# Sheet1.net
KiCad netlist of a schematic drawn in Altium Designer
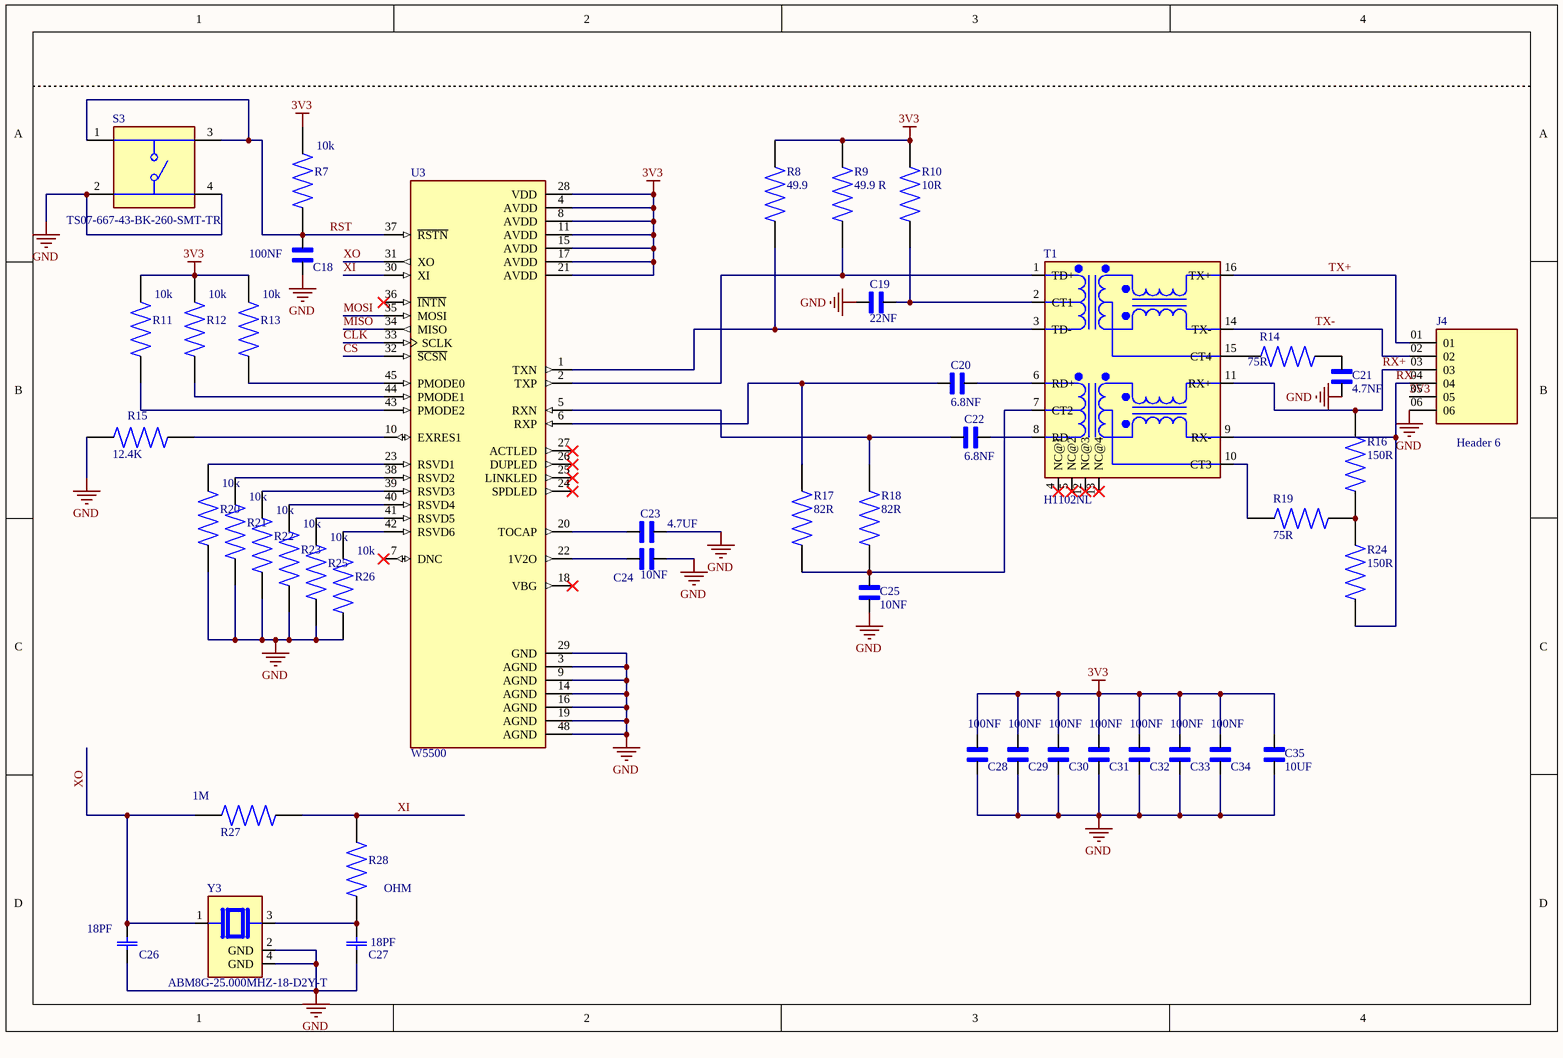
[diagram p0: Sheet1.SchDoc]

(export (version "E")
  (design (tool "Eeschema 10.0.6"))
  (components
    (comp (ref "C18")
      (value "100NF")
      (footprint "CAPC1608X90")
      (fields (field (name "MF") "KEMET") (field (name "MP") "C0603C104J3RACTU"))
      (libsource (lib "Accelo Integrated_Library") (part "C0603C104J3RACTU"))
    )
    (comp (ref "C19")
      (value "22NF")
      (footprint "CAPC1608X90")
      (fields (field (name "MF") "KEMET") (field (name "MP") "C0603C104J3RACTU"))
      (libsource (lib "") (part "C0603C104J3RACTU_1"))
    )
    (comp (ref "C20")
      (value "6.8NF")
      (footprint "CAPC1608X90")
      (fields (field (name "MF") "KEMET") (field (name "MP") "C0603C104J3RACTU"))
      (libsource (lib "") (part "C0603C104J3RACTU_1"))
    )
    (comp (ref "C21")
      (value "4.7NF")
      (footprint "CAPC1608X90")
      (fields (field (name "MF") "KEMET") (field (name "MP") "C0603C104J3RACTU"))
      (libsource (lib "") (part "C0603C104J3RACTU_2"))
    )
    (comp (ref "C22")
      (value "6.8NF")
      (footprint "CAPC1608X90")
      (fields (field (name "MF") "KEMET") (field (name "MP") "C0603C104J3RACTU"))
      (libsource (lib "") (part "C0603C104J3RACTU_1"))
    )
    (comp (ref "C23")
      (value "4.7UF")
      (footprint "CAPC2012X135N")
      (description "4.7礔 卤10% 10V Ceramic Capacitor X7R 0805 (2012 Metric)")
      (fields (field (name "MF") "Samsung") (field (name "MP") "CL21B225KPFNNNG"))
      (libsource (lib "") (part "CL21B225KPFNNNG_1"))
    )
    (comp (ref "C24")
      (value "10NF")
      (footprint "CAPC1608X90")
      (fields (field (name "MF") "KEMET") (field (name "MP") "C0603C104J3RACTU"))
      (libsource (lib "") (part "C0603C104J3RACTU_1"))
    )
    (comp (ref "C25")
      (value "10NF")
      (footprint "CAPC1608X90")
      (fields (field (name "MF") "KEMET") (field (name "MP") "C0603C104J3RACTU"))
      (libsource (lib "") (part "C0603C104J3RACTU_2"))
    )
    (comp (ref "C26")
      (value "18PF")
      (footprint "CAPC1608X85N")
      (description "18 pF ±5% 50V Ceramic Capacitor C0G, NP0 0603 (1608 Metric)")
      (fields (field (name "MF") "KEMET") (field (name "MP") "C0603C200J5GACTU"))
      (libsource (lib "Accelo Integrated_Library") (part "C0603C200J5GACTU"))
    )
    (comp (ref "C27")
      (value "18PF")
      (footprint "CAPC1608X85N")
      (description "18 pF ±5% 50V Ceramic Capacitor C0G, NP0 0603 (1608 Metric)")
      (fields (field (name "MF") "KEMET") (field (name "MP") "C0603C200J5GACTU"))
      (libsource (lib "Accelo Integrated_Library") (part "C0603C200J5GACTU"))
    )
    (comp (ref "C28")
      (value "100NF")
      (footprint "CAPC1608X90")
      (fields (field (name "MF") "KEMET") (field (name "MP") "C0603C104J3RACTU"))
      (libsource (lib "Accelo Integrated_Library") (part "C0603C104J3RACTU"))
    )
    (comp (ref "C29")
      (value "100NF")
      (footprint "CAPC1608X90")
      (fields (field (name "MF") "KEMET") (field (name "MP") "C0603C104J3RACTU"))
      (libsource (lib "Accelo Integrated_Library") (part "C0603C104J3RACTU"))
    )
    (comp (ref "C30")
      (value "100NF")
      (footprint "CAPC1608X90")
      (fields (field (name "MF") "KEMET") (field (name "MP") "C0603C104J3RACTU"))
      (libsource (lib "Accelo Integrated_Library") (part "C0603C104J3RACTU"))
    )
    (comp (ref "C31")
      (value "100NF")
      (footprint "CAPC1608X90")
      (fields (field (name "MF") "KEMET") (field (name "MP") "C0603C104J3RACTU"))
      (libsource (lib "Accelo Integrated_Library") (part "C0603C104J3RACTU"))
    )
    (comp (ref "C32")
      (value "100NF")
      (footprint "CAPC1608X90")
      (fields (field (name "MF") "KEMET") (field (name "MP") "C0603C104J3RACTU"))
      (libsource (lib "Accelo Integrated_Library") (part "C0603C104J3RACTU"))
    )
    (comp (ref "C33")
      (value "100NF")
      (footprint "CAPC1608X90")
      (fields (field (name "MF") "KEMET") (field (name "MP") "C0603C104J3RACTU"))
      (libsource (lib "Accelo Integrated_Library") (part "C0603C104J3RACTU"))
    )
    (comp (ref "C34")
      (value "100NF")
      (footprint "CAPC1608X90")
      (fields (field (name "MF") "KEMET") (field (name "MP") "C0603C104J3RACTU"))
      (libsource (lib "Accelo Integrated_Library") (part "C0603C104J3RACTU"))
    )
    (comp (ref "C35")
      (value "10UF")
      (footprint "CAPC2012X135N")
      (description "10 礔 卤10% 10V Ceramic Capacitor X7R 0805 (2012 Metric)")
      (fields (field (name "MF") "Samsung") (field (name "MP") "CL21B225KPFNNNG"))
      (libsource (lib "Accelo Integrated_Library") (part "CL21B225KPFNNNG"))
    )
    (comp (ref "J4")
      (value "Header 6")
      (footprint "SAMTEC_MTLW-106-06-G-S-180")
      (fields (field (name "MP") "MTLW-106-06-G-S-180"))
      (libsource (lib "MTLW-106-06-G-S-180") (part "MTLW-106-06-G-S-180"))
    )
    (comp (ref "R7")
      (value "10k")
      (footprint "RESC3116X65N")
      (description "10 kOhms ±1% 0.25W, 1/4W Chip Resistor 1206 (3216 Metric) Moisture Resistant Thick Film")
      (fields (field (name "MF") "Yageo") (field (name "MP") "AC1206FR-070RL"))
      (libsource (lib "Accelo Integrated_Library") (part "AC1206FR-070RL"))
    )
    (comp (ref "R8")
      (value "49.9")
      (footprint "RESC3116X65N")
      (description "49.9 Ohms ±1% 0.25W, 1/4W Chip Resistor 1206 (3216 Metric) Moisture Resistant Thick Film")
      (fields (field (name "MF") "Yageo") (field (name "MP") "AC1206FR-070RL"))
      (libsource (lib "Accelo Integrated_Library") (part "AC1206FR-070RL"))
    )
    (comp (ref "R9")
      (value "49.9 R")
      (footprint "RESC3116X65N")
      (description "49.9 Ohms ±1% 0.25W, 1/4W Chip Resistor 1206 (3216 Metric) Moisture Resistant Thick Film")
      (fields (field (name "MF") "Yageo") (field (name "MP") "AC1206FR-070RL"))
      (libsource (lib "Accelo Integrated_Library") (part "AC1206FR-070RL"))
    )
    (comp (ref "R10")
      (value "10R")
      (footprint "RESC3116X65N")
      (description "10 Ohms ±1% 0.25W, 1/4W Chip Resistor 1206 (3216 Metric) Moisture Resistant Thick Film")
      (fields (field (name "MF") "Yageo") (field (name "MP") "AC1206FR-070RL"))
      (libsource (lib "Accelo Integrated_Library") (part "AC1206FR-070RL"))
    )
    (comp (ref "R11")
      (value "10k")
      (footprint "RESC3116X65N")
      (description "10 kOhms ±1% 0.25W, 1/4W Chip Resistor 1206 (3216 Metric) Moisture Resistant Thick Film")
      (fields (field (name "MF") "Yageo") (field (name "MP") "AC1206FR-070RL"))
      (libsource (lib "Accelo Integrated_Library") (part "AC1206FR-070RL"))
    )
    (comp (ref "R12")
      (value "10k")
      (footprint "RESC3116X65N")
      (description "10 kOhms ±1% 0.25W, 1/4W Chip Resistor 1206 (3216 Metric) Moisture Resistant Thick Film")
      (fields (field (name "MF") "Yageo") (field (name "MP") "AC1206FR-070RL"))
      (libsource (lib "Accelo Integrated_Library") (part "AC1206FR-070RL"))
    )
    (comp (ref "R13")
      (value "10k")
      (footprint "RESC3116X65N")
      (description "10 kOhms ±1% 0.25W, 1/4W Chip Resistor 1206 (3216 Metric) Moisture Resistant Thick Film")
      (fields (field (name "MF") "Yageo") (field (name "MP") "AC1206FR-070RL"))
      (libsource (lib "Accelo Integrated_Library") (part "AC1206FR-070RL"))
    )
    (comp (ref "R14")
      (value "75R")
      (footprint "RESC3116X65N")
      (description "75 Ohms Jumper Chip Resistor 1206 (3216 Metric) Automotive AEC-Q200 Thick Film")
      (fields (field (name "MF") "Yageo") (field (name "MP") "AC1206FR-070RL"))
      (libsource (lib "Accelo Integrated_Library") (part "AC1206FR-070RL"))
    )
    (comp (ref "R15")
      (value "12.4K")
      (footprint "RESC3116X65N")
      (description "12.4 kOhms ±1% 0.25W, 1/4W Chip Resistor 1206 (3216 Metric) Moisture Resistant Thick Film")
      (fields (field (name "MF") "Yageo") (field (name "MP") "AC1206FR-070RL"))
      (libsource (lib "Accelo Integrated_Library") (part "AC1206FR-070RL"))
    )
    (comp (ref "R16")
      (value "150R")
      (footprint "RESC3116X65N")
      (description "150 Ohms Jumper Chip Resistor 1206 (3216 Metric) Automotive AEC-Q200 Thick Film")
      (fields (field (name "MF") "Yageo") (field (name "MP") "AC1206FR-070RL"))
      (libsource (lib "Accelo Integrated_Library") (part "AC1206FR-070RL"))
    )
    (comp (ref "R17")
      (value "82R")
      (footprint "RESC3116X65N")
      (description "82 Ohms ±1% 0.25W, 1/4W Chip Resistor 1206 (3216 Metric) Moisture Resistant Thick Film")
      (fields (field (name "MF") "Yageo") (field (name "MP") "AC1206FR-070RL"))
      (libsource (lib "Accelo Integrated_Library") (part "AC1206FR-070RL"))
    )
    (comp (ref "R18")
      (value "82R")
      (footprint "RESC3116X65N")
      (description "82 Ohms ±1% 0.25W, 1/4W Chip Resistor 1206 (3216 Metric) Moisture Resistant Thick Film")
      (fields (field (name "MF") "Yageo") (field (name "MP") "AC1206FR-070RL"))
      (libsource (lib "Accelo Integrated_Library") (part "AC1206FR-070RL"))
    )
    (comp (ref "R19")
      (value "75R")
      (footprint "RESC3116X65N")
      (description "75 Ohms Jumper Chip Resistor 1206 (3216 Metric) Automotive AEC-Q200 Thick Film")
      (fields (field (name "MF") "Yageo") (field (name "MP") "AC1206FR-070RL"))
      (libsource (lib "Accelo Integrated_Library") (part "AC1206FR-070RL"))
    )
    (comp (ref "R20")
      (value "10k")
      (footprint "RESC3116X65N")
      (description "10 kOhms ±1% 0.25W, 1/4W Chip Resistor 1206 (3216 Metric) Moisture Resistant Thick Film")
      (fields (field (name "MF") "Yageo") (field (name "MP") "AC1206FR-070RL"))
      (libsource (lib "Accelo Integrated_Library") (part "AC1206FR-070RL"))
    )
    (comp (ref "R21")
      (value "10k")
      (footprint "RESC3116X65N")
      (description "10 kOhms ±1% 0.25W, 1/4W Chip Resistor 1206 (3216 Metric) Moisture Resistant Thick Film")
      (fields (field (name "MF") "Yageo") (field (name "MP") "AC1206FR-070RL"))
      (libsource (lib "Accelo Integrated_Library") (part "AC1206FR-070RL"))
    )
    (comp (ref "R22")
      (value "10k")
      (footprint "RESC3116X65N")
      (description "10 kOhms ±1% 0.25W, 1/4W Chip Resistor 1206 (3216 Metric) Moisture Resistant Thick Film")
      (fields (field (name "MF") "Yageo") (field (name "MP") "AC1206FR-070RL"))
      (libsource (lib "Accelo Integrated_Library") (part "AC1206FR-070RL"))
    )
    (comp (ref "R23")
      (value "10k")
      (footprint "RESC3116X65N")
      (description "10 kOhms ±1% 0.25W, 1/4W Chip Resistor 1206 (3216 Metric) Moisture Resistant Thick Film")
      (fields (field (name "MF") "Yageo") (field (name "MP") "AC1206FR-070RL"))
      (libsource (lib "Accelo Integrated_Library") (part "AC1206FR-070RL"))
    )
    (comp (ref "R24")
      (value "150R")
      (footprint "RESC3116X65N")
      (description "150 Ohms Jumper Chip Resistor 1206 (3216 Metric) Automotive AEC-Q200 Thick Film")
      (fields (field (name "MF") "Yageo") (field (name "MP") "AC1206FR-070RL"))
      (libsource (lib "Accelo Integrated_Library") (part "AC1206FR-070RL"))
    )
    (comp (ref "R25")
      (value "10k")
      (footprint "RESC3116X65N")
      (description "10 kOhms ±1% 0.25W, 1/4W Chip Resistor 1206 (3216 Metric) Moisture Resistant Thick Film")
      (fields (field (name "MF") "Yageo") (field (name "MP") "AC1206FR-070RL"))
      (libsource (lib "Accelo Integrated_Library") (part "AC1206FR-070RL"))
    )
    (comp (ref "R26")
      (value "10k")
      (footprint "RESC3116X65N")
      (description "10 kOhms ±1% 0.25W, 1/4W Chip Resistor 1206 (3216 Metric) Moisture Resistant Thick Film")
      (fields (field (name "MF") "Yageo") (field (name "MP") "AC1206FR-070RL"))
      (libsource (lib "Accelo Integrated_Library") (part "AC1206FR-070RL"))
    )
    (comp (ref "R27")
      (value "1M")
      (footprint "RESC3116X65N")
      (description "1 MOhms ±1% 0.25W, 1/4W Chip Resistor 1206 (3216 Metric) Moisture Resistant Thick Film")
      (fields (field (name "MF") "Yageo") (field (name "MP") "AC1206FR-070RL"))
      (libsource (lib "Accelo Integrated_Library") (part "AC1206FR-070RL"))
    )
    (comp (ref "R28")
      (value "OHM")
      (footprint "RESC3116X65N")
      (description "0 Ohms Jumper Chip Resistor 1206 (3216 Metric) Automotive AEC-Q200 Thick Film")
      (fields (field (name "MF") "Yageo") (field (name "MP") "AC1206FR-070RL"))
      (libsource (lib "Accelo Integrated_Library") (part "AC1206FR-070RL"))
    )
    (comp (ref "S3")
      (value "TS07-667-43-BK-260-SMT-TR")
      (footprint "SW_TS07-667-43-BK-260-SMT-TR")
      (description "6 x 6.7 mm, 4.3 mm Actuator Height, 260 gf, Black, Surface Mount, SPST, Tactile Switch")
      (fields (field (name "MF") "Same Sky"))
      (libsource (lib "Accelo Integrated_Library") (part "TS07-667-43-BK-260-SMT-TR"))
    )
    (comp (ref "T1")
      (value "H1102NL")
      (footprint "H1102NL")
      (fields (field (name "MF") "Pulse"))
      (libsource (lib "H1102NL") (part "H1102NL"))
    )
    (comp (ref "U3")
      (value "W5500")
      (footprint "QFP50P900X900X160-48N")
      (description "Hardwired TCP/IP embedded Ethernet controller")
      (libsource (lib "W5500") (part "W5500"))
    )
    (comp (ref "Y3")
      (value "ABM8G-25.000MHZ-18-D2Y-T")
      (footprint "XTAL_ABM8G-25.000MHZ-18-D2Y-T")
      (description "25 MHz Â±20ppm Crystal 18pF 60 Ohms 4-SMD, No Lead")
      (fields (field (name "MF") "Abracon"))
      (libsource (lib "ABM8G-25.000MHZ-18-D2Y-T") (part "ABM8G-25.000MHZ-18-D2Y-T"))
    )
  )
  (nets
    (net (code "1") (name "/CLK") (class "Default")
      (node (ref "U3") (pin "33") (pinfunction "SCLK_33") (pintype "input"))
    )
    (net (code "2") (name "/CS") (class "Default")
      (node (ref "U3") (pin "32") (pinfunction "~{SCSN}_32") (pintype "input"))
    )
    (net (code "3") (name "/MISO") (class "Default")
      (node (ref "U3") (pin "34") (pinfunction "MISO_34") (pintype "output"))
    )
    (net (code "4") (name "/MOSI") (class "Default")
      (node (ref "U3") (pin "35") (pinfunction "MOSI_35") (pintype "input"))
    )
    (net (code "5") (name "/RST") (class "Default")
      (node (ref "C18") (pin "2") (pinfunction "2_2") (pintype "passive"))
      (node (ref "R7") (pin "1") (pinfunction "1_1") (pintype "passive"))
      (node (ref "S3") (pin "1") (pinfunction "1_1") (pintype "passive"))
      (node (ref "S3") (pin "3") (pinfunction "3_3") (pintype "passive"))
      (node (ref "U3") (pin "37") (pinfunction "~{RSTN}_37") (pintype "input"))
    )
    (net (code "6") (name "/RX+") (class "Default")
      (node (ref "J4") (pin "03") (pinfunction "03_03") (pintype "passive"))
      (node (ref "R16") (pin "1") (pinfunction "1_1") (pintype "passive"))
      (node (ref "T1") (pin "11") (pinfunction "RX+_11") (pintype "passive"))
    )
    (net (code "7") (name "/RX-") (class "Default")
      (node (ref "J4") (pin "04") (pinfunction "04_04") (pintype "passive"))
      (node (ref "R24") (pin "2") (pinfunction "2_2") (pintype "passive"))
      (node (ref "T1") (pin "9") (pinfunction "RX-_9") (pintype "passive"))
    )
    (net (code "8") (name "/TX+") (class "Default")
      (node (ref "J4") (pin "01") (pinfunction "01_01") (pintype "passive"))
      (node (ref "T1") (pin "16") (pinfunction "TX+_16") (pintype "passive"))
    )
    (net (code "9") (name "/TX-") (class "Default")
      (node (ref "J4") (pin "02") (pinfunction "02_02") (pintype "passive"))
      (node (ref "T1") (pin "14") (pinfunction "TX-_14") (pintype "passive"))
    )
    (net (code "10") (name "/XI") (class "Default")
      (node (ref "R27") (pin "1") (pinfunction "1_1") (pintype "passive"))
      (node (ref "R28") (pin "2") (pinfunction "2_2") (pintype "passive"))
      (node (ref "U3") (pin "30") (pinfunction "XI_30") (pintype "input"))
    )
    (net (code "11") (name "/XO") (class "Default")
      (node (ref "C26") (pin "2") (pinfunction "C2_2") (pintype "passive"))
      (node (ref "R27") (pin "2") (pinfunction "2_2") (pintype "passive"))
      (node (ref "U3") (pin "31") (pinfunction "XO_31") (pintype "output"))
      (node (ref "Y3") (pin "1") (pinfunction "1_1") (pintype "passive"))
    )
    (net (code "12") (name "3V3") (class "Default")
      (node (ref "C28") (pin "2") (pinfunction "2_2") (pintype "passive"))
      (node (ref "C29") (pin "2") (pinfunction "2_2") (pintype "passive"))
      (node (ref "C30") (pin "2") (pinfunction "2_2") (pintype "passive"))
      (node (ref "C31") (pin "2") (pinfunction "2_2") (pintype "passive"))
      (node (ref "C32") (pin "2") (pinfunction "2_2") (pintype "passive"))
      (node (ref "C33") (pin "2") (pinfunction "2_2") (pintype "passive"))
      (node (ref "C34") (pin "2") (pinfunction "2_2") (pintype "passive"))
      (node (ref "C35") (pin "1") (pinfunction "1_1") (pintype "passive"))
      (node (ref "J4") (pin "05") (pinfunction "05_05") (pintype "passive"))
      (node (ref "R10") (pin "1") (pinfunction "1_1") (pintype "passive"))
      (node (ref "R11") (pin "2") (pinfunction "2_2") (pintype "passive"))
      (node (ref "R12") (pin "2") (pinfunction "2_2") (pintype "passive"))
      (node (ref "R13") (pin "2") (pinfunction "2_2") (pintype "passive"))
      (node (ref "R7") (pin "2") (pinfunction "2_2") (pintype "passive"))
      (node (ref "R8") (pin "1") (pinfunction "1_1") (pintype "passive"))
      (node (ref "R9") (pin "1") (pinfunction "1_1") (pintype "passive"))
      (node (ref "U3") (pin "11") (pinfunction "AVDD_11") (pintype "power_in"))
      (node (ref "U3") (pin "15") (pinfunction "AVDD_15") (pintype "power_in"))
      (node (ref "U3") (pin "17") (pinfunction "AVDD_17") (pintype "power_in"))
      (node (ref "U3") (pin "21") (pinfunction "AVDD_21") (pintype "power_in"))
      (node (ref "U3") (pin "28") (pinfunction "VDD_28") (pintype "power_in"))
      (node (ref "U3") (pin "4") (pinfunction "AVDD_4") (pintype "power_in"))
      (node (ref "U3") (pin "8") (pinfunction "AVDD_8") (pintype "power_in"))
    )
    (net (code "13") (name "GND") (class "Default")
      (node (ref "C18") (pin "1") (pinfunction "1_1") (pintype "passive"))
      (node (ref "C19") (pin "2") (pinfunction "2_2") (pintype "passive"))
      (node (ref "C21") (pin "2") (pinfunction "2_2") (pintype "passive"))
      (node (ref "C23") (pin "2") (pinfunction "2_2") (pintype "passive"))
      (node (ref "C24") (pin "1") (pinfunction "1_1") (pintype "passive"))
      (node (ref "C25") (pin "2") (pinfunction "2_2") (pintype "passive"))
      (node (ref "C26") (pin "1") (pinfunction "C1_1") (pintype "passive"))
      (node (ref "C27") (pin "1") (pinfunction "C1_1") (pintype "passive"))
      (node (ref "C28") (pin "1") (pinfunction "1_1") (pintype "passive"))
      (node (ref "C29") (pin "1") (pinfunction "1_1") (pintype "passive"))
      (node (ref "C30") (pin "1") (pinfunction "1_1") (pintype "passive"))
      (node (ref "C31") (pin "1") (pinfunction "1_1") (pintype "passive"))
      (node (ref "C32") (pin "1") (pinfunction "1_1") (pintype "passive"))
      (node (ref "C33") (pin "1") (pinfunction "1_1") (pintype "passive"))
      (node (ref "C34") (pin "1") (pinfunction "1_1") (pintype "passive"))
      (node (ref "C35") (pin "2") (pinfunction "2_2") (pintype "passive"))
      (node (ref "J4") (pin "06") (pinfunction "06_06") (pintype "passive"))
      (node (ref "R15") (pin "2") (pinfunction "2_2") (pintype "passive"))
      (node (ref "R20") (pin "1") (pinfunction "1_1") (pintype "passive"))
      (node (ref "R21") (pin "1") (pinfunction "1_1") (pintype "passive"))
      (node (ref "R22") (pin "1") (pinfunction "1_1") (pintype "passive"))
      (node (ref "R23") (pin "1") (pinfunction "1_1") (pintype "passive"))
      (node (ref "R25") (pin "1") (pinfunction "1_1") (pintype "passive"))
      (node (ref "R26") (pin "1") (pinfunction "1_1") (pintype "passive"))
      (node (ref "S3") (pin "2") (pinfunction "2_2") (pintype "passive"))
      (node (ref "S3") (pin "4") (pinfunction "4_4") (pintype "passive"))
      (node (ref "U3") (pin "14") (pinfunction "AGND_14") (pintype "power_in"))
      (node (ref "U3") (pin "16") (pinfunction "AGND_16") (pintype "power_in"))
      (node (ref "U3") (pin "19") (pinfunction "AGND_19") (pintype "power_in"))
      (node (ref "U3") (pin "29") (pinfunction "GND_29") (pintype "passive"))
      (node (ref "U3") (pin "3") (pinfunction "AGND_3") (pintype "power_in"))
      (node (ref "U3") (pin "48") (pinfunction "AGND_48") (pintype "power_in"))
      (node (ref "U3") (pin "9") (pinfunction "AGND_9") (pintype "power_in"))
      (node (ref "Y3") (pin "2") (pinfunction "GND_2") (pintype "power_in"))
      (node (ref "Y3") (pin "4") (pinfunction "GND_4") (pintype "power_in"))
    )
    (net (code "14") (name "Net-(C21-Pad1)") (class "Default")
      (node (ref "C21") (pin "1") (pinfunction "1_1") (pintype "passive"))
      (node (ref "R14") (pin "2") (pinfunction "2_2") (pintype "passive"))
    )
    (net (code "15") (name "Net-(C27-C2)") (class "Default")
      (node (ref "C27") (pin "2") (pinfunction "C2_2") (pintype "passive"))
      (node (ref "R28") (pin "1") (pinfunction "1_1") (pintype "passive"))
      (node (ref "Y3") (pin "3") (pinfunction "2_3") (pintype "passive"))
    )
    (net (code "16") (name "Net-(R16-Pad2)") (class "Default")
      (node (ref "R16") (pin "2") (pinfunction "2_2") (pintype "passive"))
      (node (ref "R19") (pin "2") (pinfunction "2_2") (pintype "passive"))
      (node (ref "R24") (pin "1") (pinfunction "1_1") (pintype "passive"))
    )
    (net (code "17") (name "Net-(T1-CT1)") (class "Default")
      (node (ref "C19") (pin "1") (pinfunction "1_1") (pintype "passive"))
      (node (ref "R10") (pin "2") (pinfunction "2_2") (pintype "passive"))
      (node (ref "T1") (pin "2") (pinfunction "CT1_2") (pintype "passive"))
    )
    (net (code "18") (name "Net-(T1-CT2)") (class "Default")
      (node (ref "C25") (pin "1") (pinfunction "1_1") (pintype "passive"))
      (node (ref "R17") (pin "2") (pinfunction "2_2") (pintype "passive"))
      (node (ref "R18") (pin "2") (pinfunction "2_2") (pintype "passive"))
      (node (ref "T1") (pin "7") (pinfunction "CT2_7") (pintype "passive"))
    )
    (net (code "19") (name "Net-(T1-CT3)") (class "Default")
      (node (ref "R19") (pin "1") (pinfunction "1_1") (pintype "passive"))
      (node (ref "T1") (pin "10") (pinfunction "CT3_10") (pintype "passive"))
    )
    (net (code "20") (name "Net-(T1-CT4)") (class "Default")
      (node (ref "R14") (pin "1") (pinfunction "1_1") (pintype "passive"))
      (node (ref "T1") (pin "15") (pinfunction "CT4_15") (pintype "passive"))
    )
    (net (code "21") (name "Net-(T1-RD+)") (class "Default")
      (node (ref "C20") (pin "1") (pinfunction "1_1") (pintype "passive"))
      (node (ref "T1") (pin "6") (pinfunction "RD+_6") (pintype "passive"))
    )
    (net (code "22") (name "Net-(T1-RD-)") (class "Default")
      (node (ref "C22") (pin "1") (pinfunction "1_1") (pintype "passive"))
      (node (ref "T1") (pin "8") (pinfunction "RD-_8") (pintype "passive"))
    )
    (net (code "23") (name "Net-(T1-TD+)") (class "Default")
      (node (ref "R9") (pin "2") (pinfunction "2_2") (pintype "passive"))
      (node (ref "T1") (pin "1") (pinfunction "TD+_1") (pintype "passive"))
      (node (ref "U3") (pin "2") (pinfunction "TXP_2") (pintype "output"))
    )
    (net (code "24") (name "Net-(T1-TD-)") (class "Default")
      (node (ref "R8") (pin "2") (pinfunction "2_2") (pintype "passive"))
      (node (ref "T1") (pin "3") (pinfunction "TD-_3") (pintype "passive"))
      (node (ref "U3") (pin "1") (pinfunction "TXN_1") (pintype "output"))
    )
    (net (code "25") (name "Net-(U3-1V2O)") (class "Default")
      (node (ref "C24") (pin "2") (pinfunction "2_2") (pintype "passive"))
      (node (ref "U3") (pin "22") (pinfunction "1V2O_22") (pintype "output"))
    )
    (net (code "26") (name "Net-(U3-EXRES1)") (class "Default")
      (node (ref "R15") (pin "1") (pinfunction "1_1") (pintype "passive"))
      (node (ref "U3") (pin "10") (pinfunction "EXRES1_10") (pintype "bidirectional"))
    )
    (net (code "27") (name "Net-(U3-PMODE0)") (class "Default")
      (node (ref "R13") (pin "1") (pinfunction "1_1") (pintype "passive"))
      (node (ref "U3") (pin "45") (pinfunction "PMODE0_45") (pintype "input"))
    )
    (net (code "28") (name "Net-(U3-PMODE1)") (class "Default")
      (node (ref "R12") (pin "1") (pinfunction "1_1") (pintype "passive"))
      (node (ref "U3") (pin "44") (pinfunction "PMODE1_44") (pintype "input"))
    )
    (net (code "29") (name "Net-(U3-PMODE2)") (class "Default")
      (node (ref "R11") (pin "1") (pinfunction "1_1") (pintype "passive"))
      (node (ref "U3") (pin "43") (pinfunction "PMODE2_43") (pintype "input"))
    )
    (net (code "30") (name "Net-(U3-RSVD1)") (class "Default")
      (node (ref "R20") (pin "2") (pinfunction "2_2") (pintype "passive"))
      (node (ref "U3") (pin "23") (pinfunction "RSVD1_23") (pintype "input"))
    )
    (net (code "31") (name "Net-(U3-RSVD2)") (class "Default")
      (node (ref "R21") (pin "2") (pinfunction "2_2") (pintype "passive"))
      (node (ref "U3") (pin "38") (pinfunction "RSVD2_38") (pintype "input"))
    )
    (net (code "32") (name "Net-(U3-RSVD3)") (class "Default")
      (node (ref "R22") (pin "2") (pinfunction "2_2") (pintype "passive"))
      (node (ref "U3") (pin "39") (pinfunction "RSVD3_39") (pintype "input"))
    )
    (net (code "33") (name "Net-(U3-RSVD4)") (class "Default")
      (node (ref "R23") (pin "2") (pinfunction "2_2") (pintype "passive"))
      (node (ref "U3") (pin "40") (pinfunction "RSVD4_40") (pintype "input"))
    )
    (net (code "34") (name "Net-(U3-RSVD5)") (class "Default")
      (node (ref "R25") (pin "2") (pinfunction "2_2") (pintype "passive"))
      (node (ref "U3") (pin "41") (pinfunction "RSVD5_41") (pintype "input"))
    )
    (net (code "35") (name "Net-(U3-RSVD6)") (class "Default")
      (node (ref "R26") (pin "2") (pinfunction "2_2") (pintype "passive"))
      (node (ref "U3") (pin "42") (pinfunction "RSVD6_42") (pintype "input"))
    )
    (net (code "36") (name "Net-(U3-RXN)") (class "Default")
      (node (ref "C22") (pin "2") (pinfunction "2_2") (pintype "passive"))
      (node (ref "R18") (pin "1") (pinfunction "1_1") (pintype "passive"))
      (node (ref "U3") (pin "5") (pinfunction "RXN_5") (pintype "input"))
    )
    (net (code "37") (name "Net-(U3-RXP)") (class "Default")
      (node (ref "C20") (pin "2") (pinfunction "2_2") (pintype "passive"))
      (node (ref "R17") (pin "1") (pinfunction "1_1") (pintype "passive"))
      (node (ref "U3") (pin "6") (pinfunction "RXP_6") (pintype "input"))
    )
    (net (code "38") (name "Net-(U3-TOCAP)") (class "Default")
      (node (ref "C23") (pin "1") (pinfunction "1_1") (pintype "passive"))
      (node (ref "U3") (pin "20") (pinfunction "TOCAP_20") (pintype "output"))
    )
    (net (code "39") (name "unconnected-(T1-NC@1-Pad4)") (class "Default")
      (node (ref "T1") (pin "4") (pinfunction "NC@1_4") (pintype "passive+no_connect"))
    )
    (net (code "40") (name "unconnected-(T1-NC@2-Pad5)") (class "Default")
      (node (ref "T1") (pin "5") (pinfunction "NC@2_5") (pintype "passive+no_connect"))
    )
    (net (code "41") (name "unconnected-(T1-NC@3-Pad12)") (class "Default")
      (node (ref "T1") (pin "12") (pinfunction "NC@3_12") (pintype "passive+no_connect"))
    )
    (net (code "42") (name "unconnected-(T1-NC@4-Pad13)") (class "Default")
      (node (ref "T1") (pin "13") (pinfunction "NC@4_13") (pintype "passive+no_connect"))
    )
    (net (code "43") (name "unconnected-(U3-ACTLED-Pad27)") (class "Default")
      (node (ref "U3") (pin "27") (pinfunction "ACTLED_27") (pintype "output+no_connect"))
    )
    (net (code "44") (name "unconnected-(U3-DNC-Pad7)") (class "Default")
      (node (ref "U3") (pin "7") (pinfunction "DNC_7") (pintype "bidirectional+no_connect"))
    )
    (net (code "45") (name "unconnected-(U3-DUPLED-Pad26)") (class "Default")
      (node (ref "U3") (pin "26") (pinfunction "DUPLED_26") (pintype "output+no_connect"))
    )
    (net (code "46") (name "unconnected-(U3-LINKLED-Pad25)") (class "Default")
      (node (ref "U3") (pin "25") (pinfunction "LINKLED_25") (pintype "output+no_connect"))
    )
    (net (code "47") (name "unconnected-(U3-SPDLED-Pad24)") (class "Default")
      (node (ref "U3") (pin "24") (pinfunction "SPDLED_24") (pintype "output+no_connect"))
    )
    (net (code "48") (name "unconnected-(U3-VBG-Pad18)") (class "Default")
      (node (ref "U3") (pin "18") (pinfunction "VBG_18") (pintype "output+no_connect"))
    )
    (net (code "49") (name "unconnected-(U3-~{INTN}-Pad36)") (class "Default")
      (node (ref "U3") (pin "36") (pinfunction "~{INTN}_36") (pintype "input+no_connect"))
    )
  )
)
